# connectors.net
KiCad netlist of a schematic drawn in Altium Designer
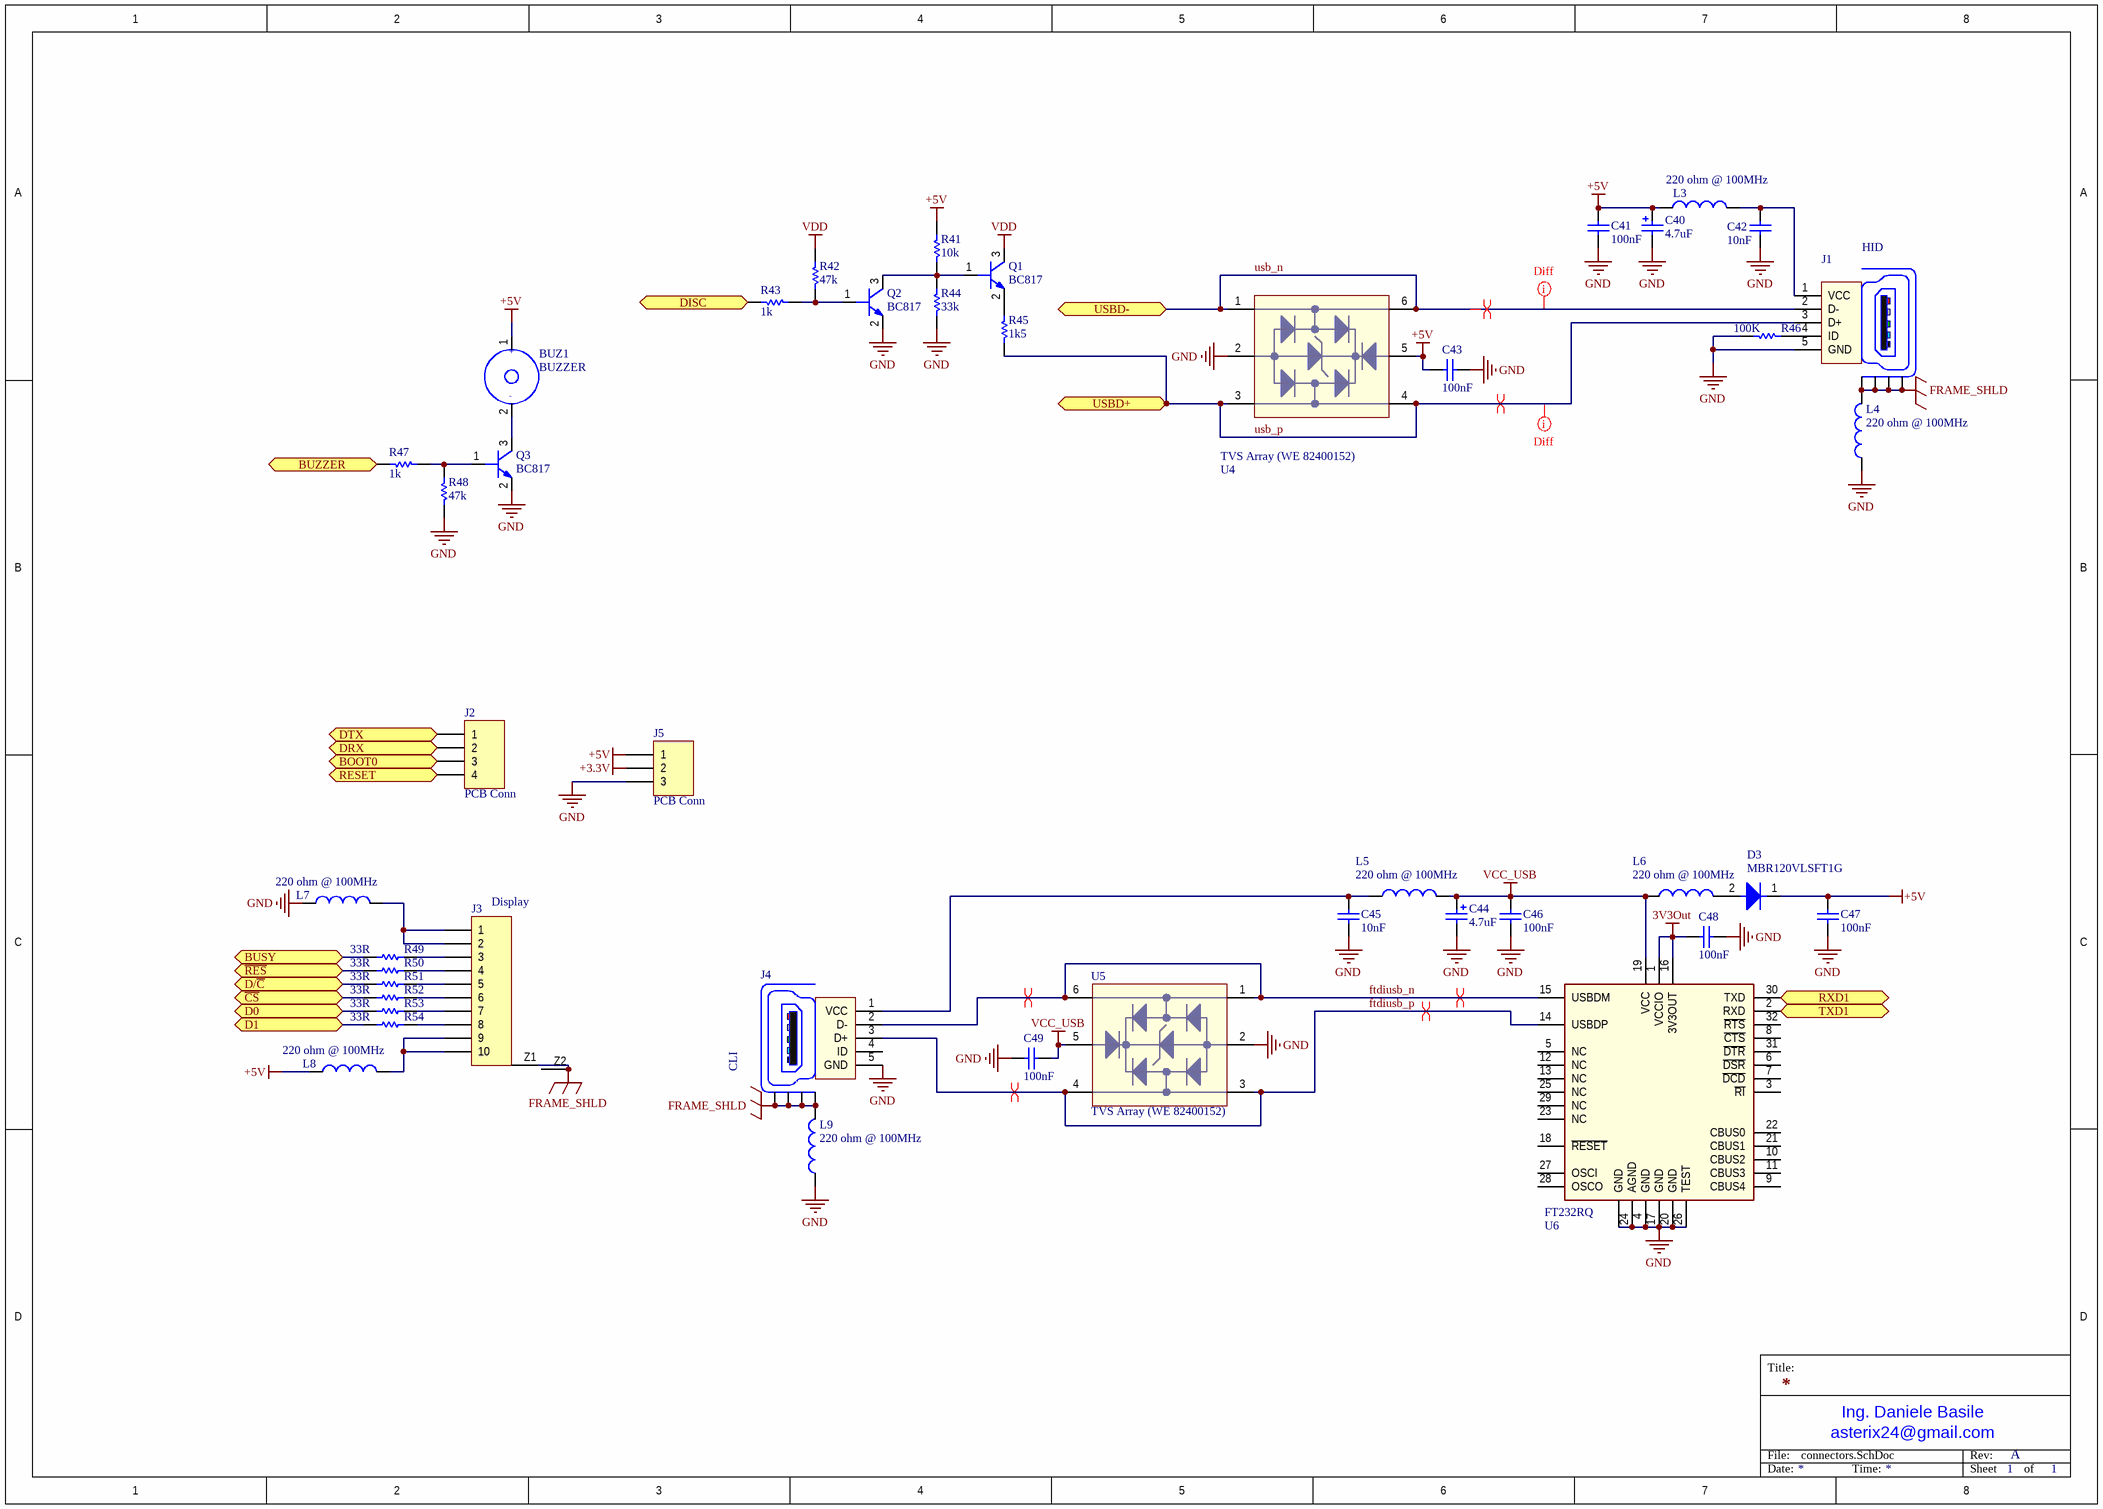
[diagram p0: connectors.SchDoc]

(export (version "E")
  (design (tool "Eeschema 10.0.6"))
  (components
    (comp (ref "BUZ1")
      (value "BUZZER")
      (footprint "buzzer_14mm_thd")
      (libsource (lib "develer_library") (part "BUZZER"))
    )
    (comp (ref "C40")
      (value "4.7uF")
      (footprint "1206_[3216]")
      (description "Ceramic X7R 16V")
      (fields (field (name "PUBLISHER") "Altium Limited"))
      (libsource (lib "DEVELER_Library") (part "Cap Pol1"))
    )
    (comp (ref "C41")
      (value "100nF")
      (footprint "0603_[1608]")
      (description "Ceramic X7R 50V")
      (fields (field (name "PUBLISHER") "Altium Limited"))
      (libsource (lib "DEVELER_Library") (part "Cap"))
    )
    (comp (ref "C42")
      (value "10nF")
      (footprint "0603_[1608]")
      (description "Ceramic X7R 50V")
      (fields (field (name "PUBLISHER") "Altium Limited"))
      (libsource (lib "DEVELER_Library") (part "Cap"))
    )
    (comp (ref "C43")
      (value "100nF")
      (footprint "0603_[1608]")
      (description "Ceramic X7R 50V")
      (fields (field (name "PUBLISHER") "Altium Limited"))
      (libsource (lib "Miscellaneous Devices") (part "Cap"))
    )
    (comp (ref "C44")
      (value "4.7uF")
      (footprint "1206_[3216]")
      (description "Ceramic X5R 25V")
      (fields (field (name "PUBLISHER") "Altium Limited"))
      (libsource (lib "DEVELER_Library") (part "Cap Pol1"))
    )
    (comp (ref "C45")
      (value "10nF")
      (footprint "0603_[1608]")
      (description "Ceramic X7R 50V")
      (fields (field (name "PUBLISHER") "Altium Limited"))
      (libsource (lib "DEVELER_Library") (part "Cap"))
    )
    (comp (ref "C46")
      (value "100nF")
      (footprint "0603_[1608]")
      (description "Ceramic X7R 50V")
      (fields (field (name "PUBLISHER") "Altium Limited"))
      (libsource (lib "DEVELER_Library") (part "Cap"))
    )
    (comp (ref "C47")
      (value "100nF")
      (footprint "0603_[1608]")
      (description "Ceramic X7R 50V")
      (fields (field (name "PUBLISHER") "Altium Limited"))
      (libsource (lib "DEVELER_Library") (part "Cap"))
    )
    (comp (ref "C48")
      (value "100nF")
      (footprint "0603_[1608]")
      (description "Ceramic X7R 50V")
      (fields (field (name "PUBLISHER") "Altium Limited"))
      (libsource (lib "DEVELER_Library") (part "Cap"))
    )
    (comp (ref "C49")
      (value "100nF")
      (footprint "0603_[1608]")
      (description "Ceramic X7R 50V")
      (fields (field (name "PUBLISHER") "Altium Limited"))
      (libsource (lib "Miscellaneous Devices") (part "Cap"))
    )
    (comp (ref "D3")
      (value "MBR120VLSFT1G")
      (footprint "SOD-123")
      (description "Diode Schottky  low Vf, If 1A (PMEG3010ER; MBRX120LF)")
      (libsource (lib "DEVELER_Library") (part "Diode"))
    )
    (comp (ref "J1")
      (value "HID")
      (footprint "usb_typeB_mini_smd")
      (description "Mini USB SMT Type B 5 Contacts")
      (fields
        (field (name "MANUFACTURER") "Würth Elektronik eiSos GmbH")
        (field (name "PARTNO") "65100516121")
        (field (name "CREATED BY") "Karrer Zheng")
      )
      (libsource (lib "develer_library") (part "USB_Con_Type_B_mini_SMT"))
    )
    (comp (ref "J2")
      (value "PCB Conn")
      (footprint "HEADER_1X4_2.54MM_THD")
      (description "Header, 4-Pin")
      (fields (field (name "PUBLISHER") "Altium Limited"))
      (libsource (lib "Miscellaneous Connectors") (part "Header 4"))
    )
    (comp (ref "J3")
      (value "Display")
      (footprint "fcc-zif_10pin_0.5mm")
      (description "Header, 10-Pin")
      (fields (field (name "PUBLISHER") "Altium Limited"))
      (libsource (lib "Miscellaneous Connectors") (part "Header 10"))
    )
    (comp (ref "J4")
      (value "CLI")
      (footprint "usb_typeB_mini_smd")
      (description "Mini USB SMT Type B 5 Contacts (WE 65100516121)")
      (fields
        (field (name "MANUFACTURER") "Würth Elektronik eiSos GmbH")
        (field (name "PARTNO") "65100516121")
        (field (name "CREATED BY") "Karrer Zheng")
      )
      (libsource (lib "DEVELER_Library") (part "USB_Con_Type_B_mini_SMT"))
    )
    (comp (ref "J5")
      (value "PCB Conn")
      (footprint "HEADER_1X3_2.54MM_THD")
      (description "Header, 3-Pin")
      (fields (field (name "PUBLISHER") "Altium Limited"))
      (libsource (lib "Miscellaneous Connectors") (part "Header 3"))
    )
    (comp (ref "L3")
      (value "220 ohm @ 100MHz")
      (footprint "0805_[2012]")
      (description "WE 742792022")
      (libsource (lib "DEVELER_Library") (part "Inductor"))
    )
    (comp (ref "L4")
      (value "220 ohm @ 100MHz")
      (footprint "0805_[2012]")
      (description "WE 742792022")
      (libsource (lib "DEVELER_Library") (part "Inductor"))
    )
    (comp (ref "L5")
      (value "220 ohm @ 100MHz")
      (footprint "0805_[2012]")
      (description "WE 742792022")
      (libsource (lib "") (part "Inductor_1"))
    )
    (comp (ref "L6")
      (value "220 ohm @ 100MHz")
      (footprint "0805_[2012]")
      (description "WE 742792022")
      (libsource (lib "") (part "Inductor_1"))
    )
    (comp (ref "L7")
      (value "220 ohm @ 100MHz")
      (footprint "0805_[2012]")
      (description "WE 742792022")
      (libsource (lib "DEVELER_Library") (part "Inductor"))
    )
    (comp (ref "L8")
      (value "220 ohm @ 100MHz")
      (footprint "0805_[2012]")
      (description "WE 742792022")
      (libsource (lib "DEVELER_Library") (part "Inductor"))
    )
    (comp (ref "L9")
      (value "220 ohm @ 100MHz")
      (footprint "0805_[2012]")
      (description "WE 742792022")
      (libsource (lib "DEVELER_Library") (part "Inductor"))
    )
    (comp (ref "Q1")
      (value "BC817")
      (footprint "SOT-23")
      (description "BJT NPN")
      (libsource (lib "develer_library") (part "BC817"))
    )
    (comp (ref "Q2")
      (value "BC817")
      (footprint "SOT-23")
      (description "BJT NPN")
      (libsource (lib "develer_library") (part "BC817"))
    )
    (comp (ref "Q3")
      (value "BC817")
      (footprint "SOT-23")
      (description "BJT NPN")
      (libsource (lib "develer_library") (part "BC817"))
    )
    (comp (ref "R41")
      (value "10k")
      (footprint "0603_[1608]")
      (description "Resistor")
      (fields (field (name "PUBLISHER") "Altium Limited"))
      (libsource (lib "DEVELER_Library") (part "Res1"))
    )
    (comp (ref "R42")
      (value "47k")
      (footprint "0603_[1608]")
      (description "Resistor")
      (fields (field (name "PUBLISHER") "Altium Limited"))
      (libsource (lib "DEVELER_Library") (part "Res1"))
    )
    (comp (ref "R43")
      (value "1k")
      (footprint "0603_[1608]")
      (description "Resistor")
      (fields (field (name "PUBLISHER") "Altium Limited"))
      (libsource (lib "DEVELER_Library") (part "Res1"))
    )
    (comp (ref "R44")
      (value "33k")
      (footprint "0603_[1608]")
      (description "Resistor")
      (fields (field (name "PUBLISHER") "Altium Limited"))
      (libsource (lib "DEVELER_Library") (part "Res1"))
    )
    (comp (ref "R45")
      (value "1k5")
      (footprint "0603_[1608]")
      (description "Resistor")
      (fields (field (name "PUBLISHER") "Altium Limited"))
      (libsource (lib "DEVELER_Library") (part "Res1"))
    )
    (comp (ref "R46")
      (value "100K")
      (footprint "0603_[1608]")
      (description "Resistor")
      (libsource (lib "Miscellaneous Devices") (part "Res1"))
    )
    (comp (ref "R47")
      (value "1k")
      (footprint "0603_[1608]")
      (description "Resistor")
      (fields (field (name "PUBLISHER") "Altium Limited"))
      (libsource (lib "DEVELER_Library") (part "Res1"))
    )
    (comp (ref "R48")
      (value "47k")
      (footprint "0603_[1608]")
      (description "Resistor")
      (fields (field (name "PUBLISHER") "Altium Limited"))
      (libsource (lib "DEVELER_Library") (part "Res1"))
    )
    (comp (ref "R49")
      (value "33R")
      (footprint "0603_[1608]")
      (description "Resistor")
      (fields (field (name "PUBLISHER") "Altium Limited"))
      (libsource (lib "simboli") (part "Res1"))
    )
    (comp (ref "R50")
      (value "33R")
      (footprint "0603_[1608]")
      (description "Resistor")
      (fields (field (name "PUBLISHER") "Altium Limited"))
      (libsource (lib "simboli") (part "Res1"))
    )
    (comp (ref "R51")
      (value "33R")
      (footprint "0603_[1608]")
      (description "Resistor")
      (fields (field (name "PUBLISHER") "Altium Limited"))
      (libsource (lib "simboli") (part "Res1"))
    )
    (comp (ref "R52")
      (value "33R")
      (footprint "0603_[1608]")
      (description "Resistor")
      (fields (field (name "PUBLISHER") "Altium Limited"))
      (libsource (lib "simboli") (part "Res1"))
    )
    (comp (ref "R53")
      (value "33R")
      (footprint "0603_[1608]")
      (description "Resistor")
      (fields (field (name "PUBLISHER") "Altium Limited"))
      (libsource (lib "simboli") (part "Res1"))
    )
    (comp (ref "R54")
      (value "33R")
      (footprint "0603_[1608]")
      (description "Resistor")
      (fields (field (name "PUBLISHER") "Altium Limited"))
      (libsource (lib "simboli") (part "Res1"))
    )
    (comp (ref "U4")
      (value "TVS Array (WE 82400152)")
      (footprint "SOT-563")
      (libsource (lib "DEVELER_Library") (part "TVS_Diode_Array"))
    )
    (comp (ref "U5")
      (value "TVS Array (WE 82400152)")
      (footprint "SOT-563")
      (libsource (lib "") (part "TVS_Diode_Array_1"))
    )
    (comp (ref "U6")
      (value "FT232RQ")
      (footprint "QFN-32")
      (description "Serial TTL 232 <-> USB (QFN-32)")
      (libsource (lib "DEVELER_Library") (part "FT232RQ"))
    )
  )
  (nets
    (net (code "1") (name "+3.3V") (class "Default")
      (node (ref "J5") (pin "2") (pinfunction "2_2") (pintype "passive"))
    )
    (net (code "2") (name "+5V") (class "Default")
      (node (ref "BUZ1") (pin "1") (pinfunction "1_1") (pintype "bidirectional"))
      (node (ref "C40") (pin "1") (pinfunction "1_1") (pintype "passive"))
      (node (ref "C41") (pin "1") (pinfunction "1_1") (pintype "passive"))
      (node (ref "C43") (pin "2") (pinfunction "2_2") (pintype "passive"))
      (node (ref "C47") (pin "2") (pinfunction "2_2") (pintype "passive"))
      (node (ref "D3") (pin "1") (pinfunction "K_1") (pintype "passive"))
      (node (ref "J5") (pin "1") (pinfunction "1_1") (pintype "passive"))
      (node (ref "L3") (pin "1") (pinfunction "1_1") (pintype "passive"))
      (node (ref "L8") (pin "1") (pinfunction "1_1") (pintype "passive"))
      (node (ref "R41") (pin "1") (pinfunction "1_1") (pintype "passive"))
      (node (ref "U4") (pin "5") (pinfunction "5_5") (pintype "passive"))
    )
    (net (code "3") (name "/BOOT0") (class "Default")
      (node (ref "J2") (pin "3") (pinfunction "3_3") (pintype "passive"))
    )
    (net (code "4") (name "/BUSY") (class "Default")
      (node (ref "R49") (pin "2") (pinfunction "2_2") (pintype "passive"))
    )
    (net (code "5") (name "/BUZZER") (class "Default")
      (node (ref "R47") (pin "2") (pinfunction "2_2") (pintype "passive"))
    )
    (net (code "6") (name "/D0") (class "Default")
      (node (ref "R53") (pin "2") (pinfunction "2_2") (pintype "passive"))
    )
    (net (code "7") (name "/D1") (class "Default")
      (node (ref "R54") (pin "2") (pinfunction "2_2") (pintype "passive"))
    )
    (net (code "8") (name "/DISC") (class "Default")
      (node (ref "R43") (pin "2") (pinfunction "2_2") (pintype "passive"))
    )
    (net (code "9") (name "/DRX") (class "Default")
      (node (ref "J2") (pin "2") (pinfunction "2_2") (pintype "passive"))
    )
    (net (code "10") (name "/DTX") (class "Default")
      (node (ref "J2") (pin "1") (pinfunction "1_1") (pintype "passive"))
    )
    (net (code "11") (name "/D{slash}~{C}") (class "Default")
      (node (ref "R51") (pin "2") (pinfunction "2_2") (pintype "passive"))
    )
    (net (code "12") (name "/RESET") (class "Default")
      (node (ref "J2") (pin "4") (pinfunction "4_4") (pintype "passive"))
    )
    (net (code "13") (name "/RXD1") (class "Default")
      (node (ref "U6") (pin "30") (pinfunction "TXD_30") (pintype "passive"))
    )
    (net (code "14") (name "/TXD1") (class "Default")
      (node (ref "U6") (pin "2") (pinfunction "RXD_2") (pintype "passive"))
    )
    (net (code "15") (name "/ftdiusb_n") (class "Default")
      (node (ref "J4") (pin "2") (pinfunction "D-_2") (pintype "passive"))
      (node (ref "U5") (pin "1") (pinfunction "1_1") (pintype "passive"))
      (node (ref "U5") (pin "6") (pinfunction "6_6") (pintype "passive"))
      (node (ref "U6") (pin "15") (pinfunction "USBDM_15") (pintype "passive"))
    )
    (net (code "16") (name "/ftdiusb_p") (class "Default")
      (node (ref "J4") (pin "3") (pinfunction "D+_3") (pintype "passive"))
      (node (ref "U5") (pin "3") (pinfunction "3_3") (pintype "passive"))
      (node (ref "U5") (pin "4") (pinfunction "4_4") (pintype "passive"))
      (node (ref "U6") (pin "14") (pinfunction "USBDP_14") (pintype "passive"))
    )
    (net (code "17") (name "/usb_n") (class "Default")
      (node (ref "J1") (pin "2") (pinfunction "D-_2") (pintype "passive"))
      (node (ref "U4") (pin "1") (pinfunction "1_1") (pintype "passive"))
      (node (ref "U4") (pin "6") (pinfunction "6_6") (pintype "passive"))
    )
    (net (code "18") (name "/usb_p") (class "Default")
      (node (ref "J1") (pin "3") (pinfunction "D+_3") (pintype "passive"))
      (node (ref "R45") (pin "2") (pinfunction "2_2") (pintype "passive"))
      (node (ref "U4") (pin "3") (pinfunction "3_3") (pintype "passive"))
      (node (ref "U4") (pin "4") (pinfunction "4_4") (pintype "passive"))
    )
    (net (code "19") (name "/~{CS}") (class "Default")
      (node (ref "R52") (pin "2") (pinfunction "2_2") (pintype "passive"))
    )
    (net (code "20") (name "/~{RES}") (class "Default")
      (node (ref "R50") (pin "2") (pinfunction "2_2") (pintype "passive"))
    )
    (net (code "21") (name "3V3Out") (class "Default")
      (node (ref "C48") (pin "1") (pinfunction "1_1") (pintype "passive"))
      (node (ref "U6") (pin "1") (pinfunction "VCCIO_1") (pintype "passive"))
      (node (ref "U6") (pin "16") (pinfunction "3V3OUT_16") (pintype "passive"))
    )
    (net (code "22") (name "FRAME_SHLD") (class "Default")
      (node (ref "J1") (pin "Z1") (pinfunction "Shield_Z1") (pintype "passive"))
      (node (ref "J1") (pin "Z2") (pinfunction "Shield_Z2") (pintype "passive"))
      (node (ref "J1") (pin "Z3") (pinfunction "Shield_Z3") (pintype "passive"))
      (node (ref "J1") (pin "Z4") (pinfunction "Shield_Z4") (pintype "passive"))
      (node (ref "J3") (pin "Z1") (pinfunction "Z1_Z1") (pintype "passive"))
      (node (ref "J3") (pin "Z2") (pinfunction "Z2_Z2") (pintype "passive"))
      (node (ref "J4") (pin "Z1") (pinfunction "Shield_Z1") (pintype "passive"))
      (node (ref "J4") (pin "Z2") (pinfunction "Shield_Z2") (pintype "passive"))
      (node (ref "J4") (pin "Z3") (pinfunction "Shield_Z3") (pintype "passive"))
      (node (ref "J4") (pin "Z4") (pinfunction "Shield_Z4") (pintype "passive"))
      (node (ref "L4") (pin "2") (pinfunction "2_2") (pintype "passive"))
      (node (ref "L9") (pin "2") (pinfunction "2_2") (pintype "passive"))
    )
    (net (code "23") (name "GND") (class "Default")
      (node (ref "C40") (pin "2") (pinfunction "2_2") (pintype "passive"))
      (node (ref "C41") (pin "2") (pinfunction "2_2") (pintype "passive"))
      (node (ref "C42") (pin "2") (pinfunction "2_2") (pintype "passive"))
      (node (ref "C43") (pin "1") (pinfunction "1_1") (pintype "passive"))
      (node (ref "C44") (pin "2") (pinfunction "2_2") (pintype "passive"))
      (node (ref "C45") (pin "2") (pinfunction "2_2") (pintype "passive"))
      (node (ref "C46") (pin "2") (pinfunction "2_2") (pintype "passive"))
      (node (ref "C47") (pin "1") (pinfunction "1_1") (pintype "passive"))
      (node (ref "C48") (pin "2") (pinfunction "2_2") (pintype "passive"))
      (node (ref "C49") (pin "1") (pinfunction "1_1") (pintype "passive"))
      (node (ref "J1") (pin "5") (pinfunction "GND_5") (pintype "passive"))
      (node (ref "J4") (pin "5") (pinfunction "GND_5") (pintype "passive"))
      (node (ref "J5") (pin "3") (pinfunction "3_3") (pintype "passive"))
      (node (ref "L4") (pin "1") (pinfunction "1_1") (pintype "passive"))
      (node (ref "L7") (pin "1") (pinfunction "1_1") (pintype "passive"))
      (node (ref "L9") (pin "1") (pinfunction "1_1") (pintype "passive"))
      (node (ref "Q2") (pin "2") (pinfunction "E_2") (pintype "passive"))
      (node (ref "Q3") (pin "2") (pinfunction "E_2") (pintype "passive"))
      (node (ref "R44") (pin "2") (pinfunction "2_2") (pintype "passive"))
      (node (ref "R46") (pin "2") (pinfunction "2_2") (pintype "passive"))
      (node (ref "R48") (pin "2") (pinfunction "2_2") (pintype "passive"))
      (node (ref "U4") (pin "2") (pinfunction "2_2") (pintype "passive"))
      (node (ref "U5") (pin "2") (pinfunction "2_2") (pintype "passive"))
      (node (ref "U6") (pin "17") (pinfunction "GND_17") (pintype "passive"))
      (node (ref "U6") (pin "20") (pinfunction "GND_20") (pintype "passive"))
      (node (ref "U6") (pin "24") (pinfunction "AGND_24") (pintype "passive"))
      (node (ref "U6") (pin "26") (pinfunction "TEST_26") (pintype "passive"))
      (node (ref "U6") (pin "4") (pinfunction "GND_4") (pintype "passive"))
      (node (ref "U6") (pin "GND_PAD") (pinfunction "GND_GND_PAD") (pintype "passive"))
    )
    (net (code "24") (name "Net-(D3-A)") (class "Default")
      (node (ref "D3") (pin "2") (pinfunction "A_2") (pintype "passive"))
      (node (ref "L6") (pin "1") (pinfunction "1_1") (pintype "passive"))
    )
    (net (code "25") (name "Net-(J1-ID)") (class "Default")
      (node (ref "J1") (pin "4") (pinfunction "ID_4") (pintype "passive"))
      (node (ref "R46") (pin "1") (pinfunction "1_1") (pintype "passive"))
    )
    (net (code "26") (name "Net-(J1-VCC)") (class "Default")
      (node (ref "C42") (pin "1") (pinfunction "1_1") (pintype "passive"))
      (node (ref "J1") (pin "1") (pinfunction "VCC_1") (pintype "passive"))
      (node (ref "L3") (pin "2") (pinfunction "2_2") (pintype "passive"))
    )
    (net (code "27") (name "Net-(J3-Pad1)") (class "Default")
      (node (ref "J3") (pin "1") (pinfunction "1_1") (pintype "passive"))
      (node (ref "J3") (pin "2") (pinfunction "2_2") (pintype "passive"))
      (node (ref "L7") (pin "2") (pinfunction "2_2") (pintype "passive"))
    )
    (net (code "28") (name "Net-(J3-Pad3)") (class "Default")
      (node (ref "J3") (pin "3") (pinfunction "3_3") (pintype "passive"))
      (node (ref "R49") (pin "1") (pinfunction "1_1") (pintype "passive"))
    )
    (net (code "29") (name "Net-(J3-Pad4)") (class "Default")
      (node (ref "J3") (pin "4") (pinfunction "4_4") (pintype "passive"))
      (node (ref "R50") (pin "1") (pinfunction "1_1") (pintype "passive"))
    )
    (net (code "30") (name "Net-(J3-Pad5)") (class "Default")
      (node (ref "J3") (pin "5") (pinfunction "5_5") (pintype "passive"))
      (node (ref "R51") (pin "1") (pinfunction "1_1") (pintype "passive"))
    )
    (net (code "31") (name "Net-(J3-Pad6)") (class "Default")
      (node (ref "J3") (pin "6") (pinfunction "6_6") (pintype "passive"))
      (node (ref "R52") (pin "1") (pinfunction "1_1") (pintype "passive"))
    )
    (net (code "32") (name "Net-(J3-Pad7)") (class "Default")
      (node (ref "J3") (pin "7") (pinfunction "7_7") (pintype "passive"))
      (node (ref "R53") (pin "1") (pinfunction "1_1") (pintype "passive"))
    )
    (net (code "33") (name "Net-(J3-Pad8)") (class "Default")
      (node (ref "J3") (pin "8") (pinfunction "8_8") (pintype "passive"))
      (node (ref "R54") (pin "1") (pinfunction "1_1") (pintype "passive"))
    )
    (net (code "34") (name "Net-(J3-Pad10)") (class "Default")
      (node (ref "J3") (pin "10") (pinfunction "10_10") (pintype "passive"))
      (node (ref "J3") (pin "9") (pinfunction "9_9") (pintype "passive"))
      (node (ref "L8") (pin "2") (pinfunction "2_2") (pintype "passive"))
    )
    (net (code "35") (name "Net-(J4-VCC)") (class "Default")
      (node (ref "C45") (pin "1") (pinfunction "1_1") (pintype "passive"))
      (node (ref "J4") (pin "1") (pinfunction "VCC_1") (pintype "passive"))
      (node (ref "L5") (pin "2") (pinfunction "2_2") (pintype "passive"))
    )
    (net (code "36") (name "Net-(Q1-B)") (class "Default")
      (node (ref "Q1") (pin "1") (pinfunction "B_1") (pintype "passive"))
      (node (ref "Q2") (pin "3") (pinfunction "C_3") (pintype "passive"))
      (node (ref "R41") (pin "2") (pinfunction "2_2") (pintype "passive"))
      (node (ref "R44") (pin "1") (pinfunction "1_1") (pintype "passive"))
    )
    (net (code "37") (name "Net-(Q1-E)") (class "Default")
      (node (ref "Q1") (pin "2") (pinfunction "E_2") (pintype "passive"))
      (node (ref "R45") (pin "1") (pinfunction "1_1") (pintype "passive"))
    )
    (net (code "38") (name "Net-(Q2-B)") (class "Default")
      (node (ref "Q2") (pin "1") (pinfunction "B_1") (pintype "passive"))
      (node (ref "R42") (pin "2") (pinfunction "2_2") (pintype "passive"))
      (node (ref "R43") (pin "1") (pinfunction "1_1") (pintype "passive"))
    )
    (net (code "39") (name "Net-(Q3-B)") (class "Default")
      (node (ref "Q3") (pin "1") (pinfunction "B_1") (pintype "passive"))
      (node (ref "R47") (pin "1") (pinfunction "1_1") (pintype "passive"))
      (node (ref "R48") (pin "1") (pinfunction "1_1") (pintype "passive"))
    )
    (net (code "40") (name "Net-(Q3-C)") (class "Default")
      (node (ref "BUZ1") (pin "2") (pinfunction "2_2") (pintype "bidirectional"))
      (node (ref "Q3") (pin "3") (pinfunction "C_3") (pintype "passive"))
    )
    (net (code "41") (name "VCC_USB") (class "Default")
      (node (ref "C44") (pin "1") (pinfunction "1_1") (pintype "passive"))
      (node (ref "C46") (pin "1") (pinfunction "1_1") (pintype "passive"))
      (node (ref "C49") (pin "2") (pinfunction "2_2") (pintype "passive"))
      (node (ref "L5") (pin "1") (pinfunction "1_1") (pintype "passive"))
      (node (ref "L6") (pin "2") (pinfunction "2_2") (pintype "passive"))
      (node (ref "U5") (pin "5") (pinfunction "5_5") (pintype "passive"))
      (node (ref "U6") (pin "19") (pinfunction "VCC_19") (pintype "passive"))
    )
    (net (code "42") (name "VDD") (class "Default")
      (node (ref "Q1") (pin "3") (pinfunction "C_3") (pintype "passive"))
      (node (ref "R42") (pin "1") (pinfunction "1_1") (pintype "passive"))
    )
    (net (code "43") (name "unconnected-(J4-ID-Pad4)") (class "Default")
      (node (ref "J4") (pin "4") (pinfunction "ID_4") (pintype "passive"))
    )
    (net (code "44") (name "unconnected-(U6-CBUS0-Pad22)") (class "Default")
      (node (ref "U6") (pin "22") (pinfunction "CBUS0_22") (pintype "passive"))
    )
    (net (code "45") (name "unconnected-(U6-CBUS1-Pad21)") (class "Default")
      (node (ref "U6") (pin "21") (pinfunction "CBUS1_21") (pintype "passive"))
    )
    (net (code "46") (name "unconnected-(U6-CBUS2-Pad10)") (class "Default")
      (node (ref "U6") (pin "10") (pinfunction "CBUS2_10") (pintype "passive"))
    )
    (net (code "47") (name "unconnected-(U6-CBUS3-Pad11)") (class "Default")
      (node (ref "U6") (pin "11") (pinfunction "CBUS3_11") (pintype "passive"))
    )
    (net (code "48") (name "unconnected-(U6-CBUS4-Pad9)") (class "Default")
      (node (ref "U6") (pin "9") (pinfunction "CBUS4_9") (pintype "passive"))
    )
    (net (code "49") (name "unconnected-(U6-NC-Pad5)") (class "Default")
      (node (ref "U6") (pin "5") (pinfunction "NC_5") (pintype "passive"))
    )
    (net (code "50") (name "unconnected-(U6-NC-Pad12)") (class "Default")
      (node (ref "U6") (pin "12") (pinfunction "NC_12") (pintype "passive"))
    )
    (net (code "51") (name "unconnected-(U6-NC-Pad13)") (class "Default")
      (node (ref "U6") (pin "13") (pinfunction "NC_13") (pintype "passive"))
    )
    (net (code "52") (name "unconnected-(U6-NC-Pad23)") (class "Default")
      (node (ref "U6") (pin "23") (pinfunction "NC_23") (pintype "passive"))
    )
    (net (code "53") (name "unconnected-(U6-NC-Pad25)") (class "Default")
      (node (ref "U6") (pin "25") (pinfunction "NC_25") (pintype "passive"))
    )
    (net (code "54") (name "unconnected-(U6-NC-Pad29)") (class "Default")
      (node (ref "U6") (pin "29") (pinfunction "NC_29") (pintype "passive"))
    )
    (net (code "55") (name "unconnected-(U6-OSCI-Pad27)") (class "Default")
      (node (ref "U6") (pin "27") (pinfunction "OSCI_27") (pintype "passive"))
    )
    (net (code "56") (name "unconnected-(U6-OSCO-Pad28)") (class "Default")
      (node (ref "U6") (pin "28") (pinfunction "OSCO_28") (pintype "passive"))
    )
    (net (code "57") (name "unconnected-(U6-~{CTS}-Pad8)") (class "Default")
      (node (ref "U6") (pin "8") (pinfunction "~{CTS}_8") (pintype "passive"))
    )
    (net (code "58") (name "unconnected-(U6-~{DCD}-Pad7)") (class "Default")
      (node (ref "U6") (pin "7") (pinfunction "~{DCD}_7") (pintype "passive"))
    )
    (net (code "59") (name "unconnected-(U6-~{DSR}-Pad6)") (class "Default")
      (node (ref "U6") (pin "6") (pinfunction "~{DSR}_6") (pintype "passive"))
    )
    (net (code "60") (name "unconnected-(U6-~{DTR}-Pad31)") (class "Default")
      (node (ref "U6") (pin "31") (pinfunction "~{DTR}_31") (pintype "passive"))
    )
    (net (code "61") (name "unconnected-(U6-~{RESET}-Pad18)") (class "Default")
      (node (ref "U6") (pin "18") (pinfunction "~{RESET}_18") (pintype "passive"))
    )
    (net (code "62") (name "unconnected-(U6-~{RI}-Pad3)") (class "Default")
      (node (ref "U6") (pin "3") (pinfunction "~{RI}_3") (pintype "passive"))
    )
    (net (code "63") (name "unconnected-(U6-~{RTS}-Pad32)") (class "Default")
      (node (ref "U6") (pin "32") (pinfunction "~{RTS}_32") (pintype "passive"))
    )
  )
)
